# 4_STM32_Peripheral.net
KiCad netlist of a schematic drawn in Altium Designer
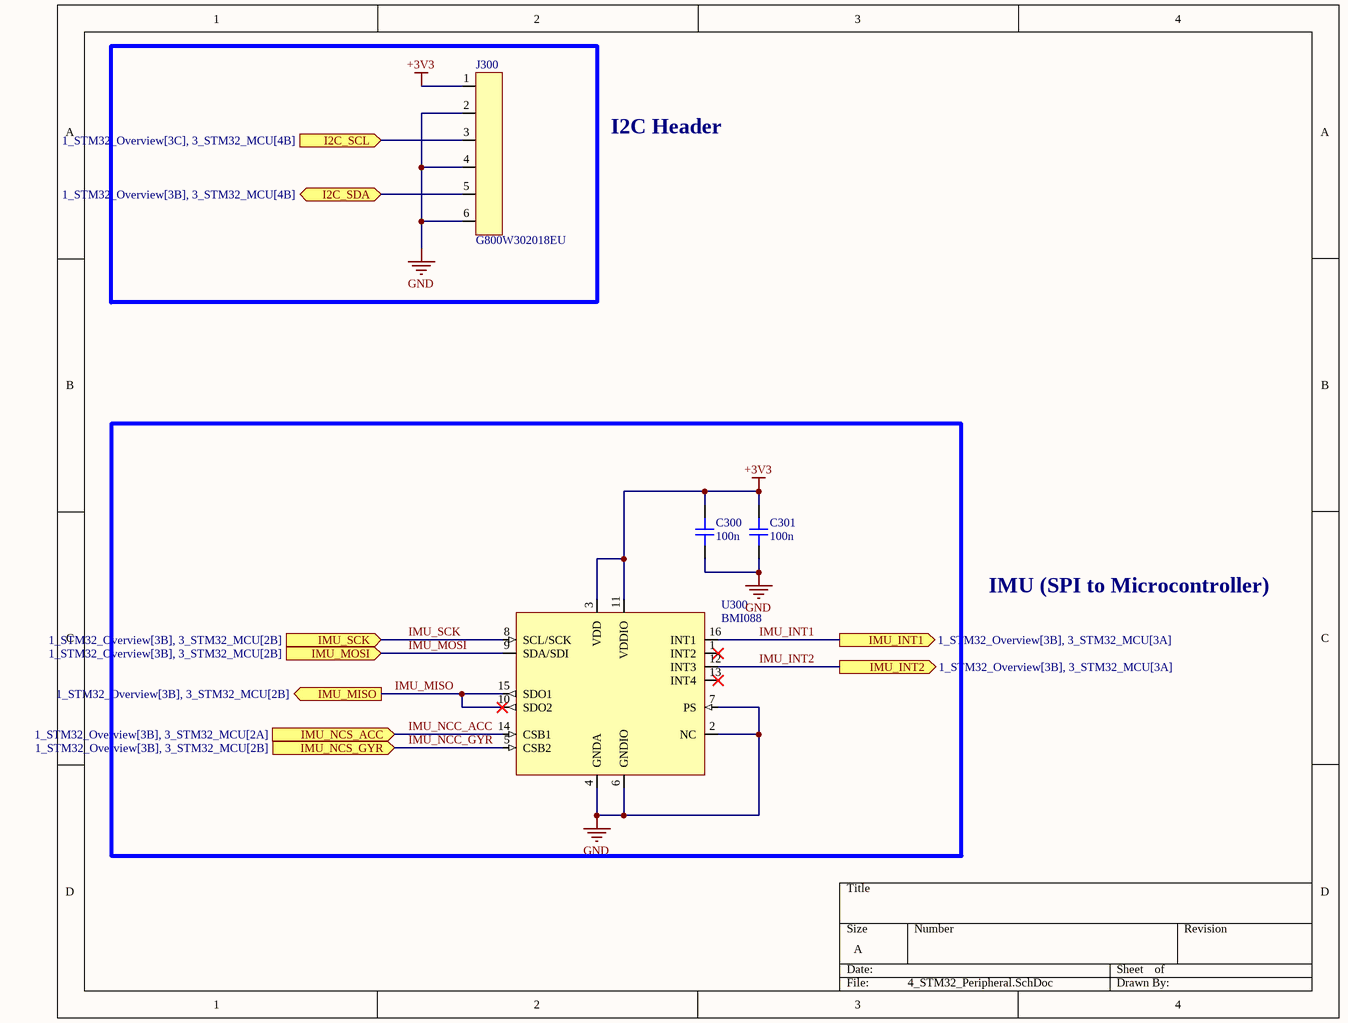
[diagram p0: 4_STM32_Peripheral.SchDoc]

(export (version "E")
  (design (tool "Eeschema 10.0.6"))
  (components
    (comp (ref "C300")
      (value "100n")
      (footprint "CAP_0603")
      (description "Capacitor SMD 0603")
      (fields (field (name "SOURCE") "Schematic-Lib-PhilsLab.SchLib"))
      (libsource (lib "Industrial University of Ho Chi Minh City") (part "CAP_EL_NP_5MM"))
    )
    (comp (ref "C301")
      (value "100n")
      (footprint "CAP_0603")
      (description "Capacitor SMD 0603")
      (fields (field (name "SOURCE") "Schematic-Lib-PhilsLab.SchLib"))
      (libsource (lib "Industrial University of Ho Chi Minh City") (part "CAP_EL_NP_5MM"))
    )
    (comp (ref "J300")
      (value "G800W302018EU")
      (footprint "G800W302018EU")
      (description "Pin Header 6 Position 2.54mm Pitch")
      (fields
        (field (name "MANUFACTURER") "Amphenol")
        (field (name "SOURCE") "Schematic-Lib-PhilsLab.SchLib")
      )
      (libsource (lib "Industrial University of Ho Chi Minh City") (part "801-87-006-10-012101"))
    )
    (comp (ref "U300")
      (value "BMI088")
      (footprint "BMI088")
      (description "Inertial Measurement Unit IMU 6-Axis LGA")
      (fields (field (name "MANUFACTURER") "Bosch") (field (name "SOURCE") "Schematic-Lib-PhilsLab.SchLib"))
      (libsource (lib "Industrial University of Ho Chi Minh City") (part "BMI088"))
    )
  )
  (nets
    (net (code "1") (name "+3V3") (class "Default")
      (node (ref "C300") (pin "2") (pinfunction "2_2") (pintype "passive"))
      (node (ref "C301") (pin "2") (pinfunction "2_2") (pintype "passive"))
      (node (ref "J300") (pin "1") (pinfunction "1_1") (pintype "passive"))
      (node (ref "U300") (pin "11") (pinfunction "VDDIO_11") (pintype "power_in"))
      (node (ref "U300") (pin "3") (pinfunction "VDD_3") (pintype "power_in"))
    )
    (net (code "2") (name "/I2C_SCL") (class "Default")
      (node (ref "J300") (pin "3") (pinfunction "3_3") (pintype "passive"))
    )
    (net (code "3") (name "/I2C_SDA") (class "Default")
      (node (ref "J300") (pin "5") (pinfunction "5_5") (pintype "passive"))
    )
    (net (code "4") (name "/IMU_INT1") (class "Default")
      (node (ref "U300") (pin "16") (pinfunction "INT1_16") (pintype "bidirectional"))
    )
    (net (code "5") (name "/IMU_INT2") (class "Default")
      (node (ref "U300") (pin "12") (pinfunction "INT3_12") (pintype "bidirectional"))
    )
    (net (code "6") (name "/IMU_MISO") (class "Default")
      (node (ref "U300") (pin "10") (pinfunction "SDO2_10") (pintype "output"))
      (node (ref "U300") (pin "15") (pinfunction "SDO1_15") (pintype "output"))
    )
    (net (code "7") (name "/IMU_MOSI") (class "Default")
      (node (ref "U300") (pin "9") (pinfunction "SDA/SDI_9") (pintype "bidirectional"))
    )
    (net (code "8") (name "/IMU_NCC_ACC") (class "Default")
      (node (ref "U300") (pin "14") (pinfunction "CSB1_14") (pintype "input"))
    )
    (net (code "9") (name "/IMU_NCC_GYR") (class "Default")
      (node (ref "U300") (pin "5") (pinfunction "CSB2_5") (pintype "input"))
    )
    (net (code "10") (name "/IMU_SCK") (class "Default")
      (node (ref "U300") (pin "8") (pinfunction "SCL/SCK_8") (pintype "input"))
    )
    (net (code "11") (name "GND") (class "Default")
      (node (ref "C300") (pin "1") (pinfunction "1_1") (pintype "passive"))
      (node (ref "C301") (pin "1") (pinfunction "1_1") (pintype "passive"))
      (node (ref "J300") (pin "2") (pinfunction "2_2") (pintype "passive"))
      (node (ref "J300") (pin "4") (pinfunction "4_4") (pintype "passive"))
      (node (ref "J300") (pin "6") (pinfunction "6_6") (pintype "passive"))
      (node (ref "U300") (pin "2") (pinfunction "NC_2") (pintype "passive"))
      (node (ref "U300") (pin "4") (pinfunction "GNDA_4") (pintype "power_in"))
      (node (ref "U300") (pin "6") (pinfunction "GNDIO_6") (pintype "power_in"))
      (node (ref "U300") (pin "7") (pinfunction "PS_7") (pintype "input"))
    )
    (net (code "12") (name "unconnected-(U300-INT2-Pad1)") (class "Default")
      (node (ref "U300") (pin "1") (pinfunction "INT2_1") (pintype "bidirectional+no_connect"))
    )
    (net (code "13") (name "unconnected-(U300-INT4-Pad13)") (class "Default")
      (node (ref "U300") (pin "13") (pinfunction "INT4_13") (pintype "bidirectional+no_connect"))
    )
  )
)
